# Combined_Board_BMI088.net
KiCad netlist of a schematic drawn in EAGLE
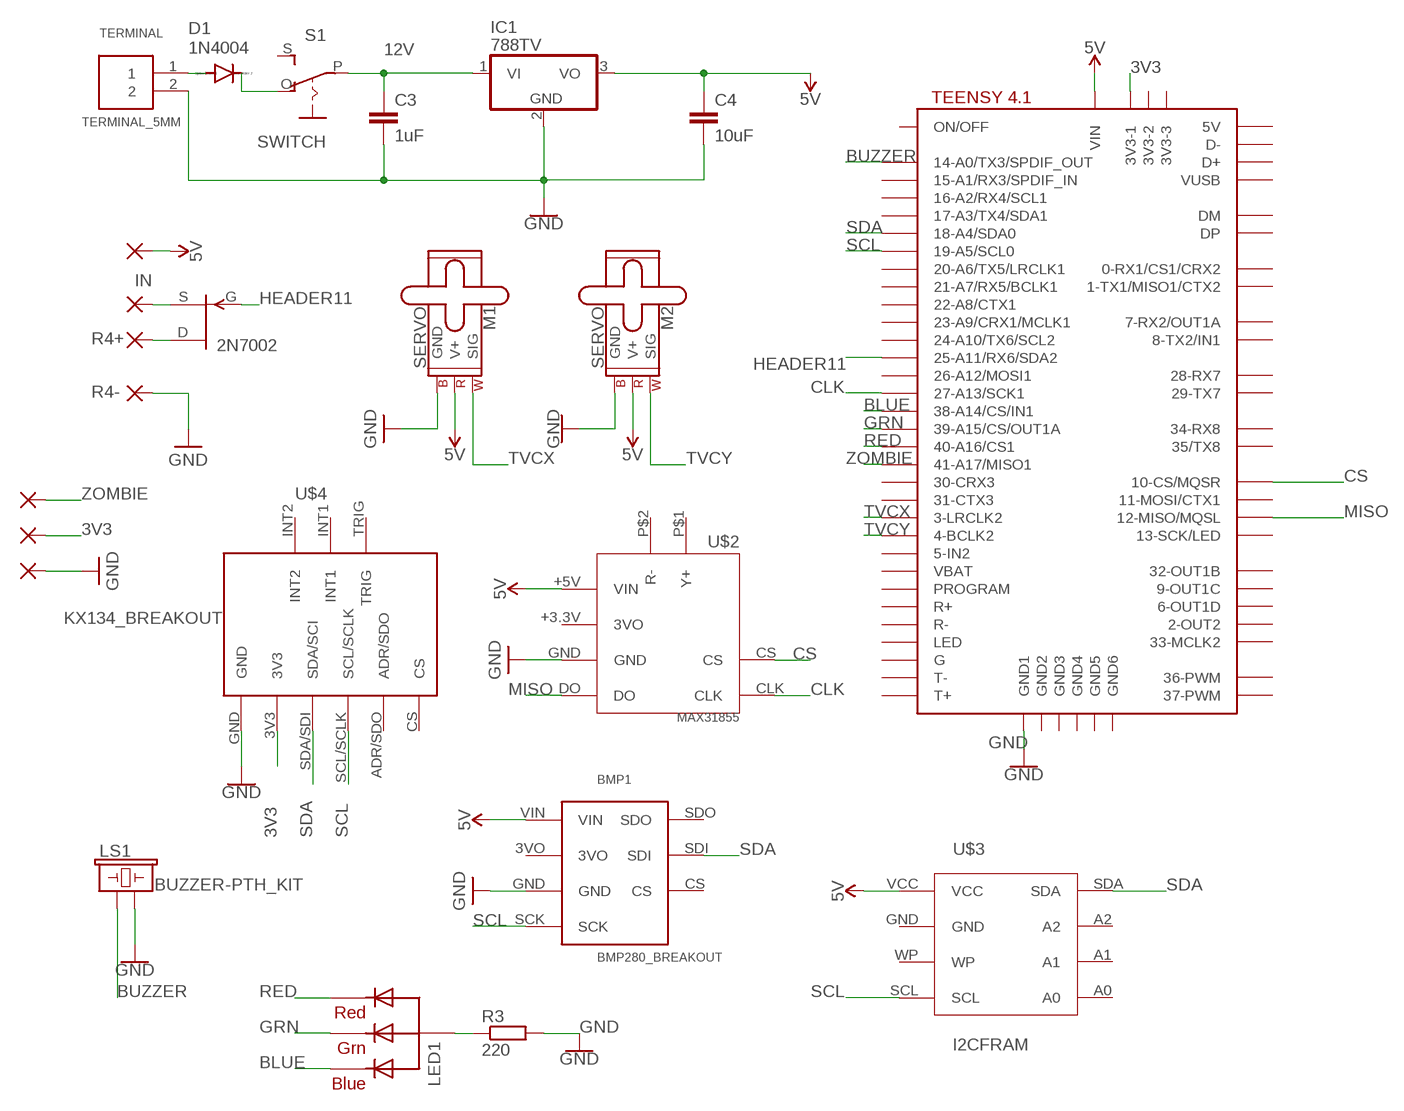
[diagram p0: schematic, sheet 1]

(export (version "E")
  (design (tool "Eeschema 10.0.6"))
  (components
    (comp (ref "2N7002")
      (value "2N3819")
      (footprint "eagle-import:TO92")
      (libsource (lib "eagle-import") (part "2N3819"))
    )
    (comp (ref "5V")
      (value "0")
      (footprint "eagle-import:1,6_0,8")
      (libsource (lib "eagle-import") (part "1,6/0,8"))
    )
    (comp (ref "BMP1")
      (value "BMP280_BREAKOUT")
      (footprint "eagle-import:BMP280_BREAKOUT")
      (libsource (lib "eagle-import") (part "BMP280_BREAKOUT"))
    )
    (comp (ref "C3")
      (value "1uF")
      (footprint "eagle-import:CAP-PTH-2.54")
      (libsource (lib "eagle-import") (part "22PF-PTH-2.54MM-200V-5%"))
    )
    (comp (ref "C4")
      (value "10uF")
      (footprint "eagle-import:CAP-PTH-2.54")
      (libsource (lib "eagle-import") (part "22PF-PTH-2.54MM-200V-5%"))
    )
    (comp (ref "D1")
      (value "1N4004")
      (footprint "eagle-import:DO41-10")
      (libsource (lib "eagle-import") (part "1N4004"))
    )
    (comp (ref "IC1")
      (value "788TV")
      (footprint "eagle-import:TO220V")
      (libsource (lib "eagle-import") (part "78TV8"))
    )
    (comp (ref "IN")
      (value "0")
      (footprint "eagle-import:1,6_0,8")
      (libsource (lib "eagle-import") (part "1,6/0,8"))
    )
    (comp (ref "LED1")
      (value "RGBLED_CA-5MM")
      (footprint "eagle-import:LED5MMRGB")
      (libsource (lib "eagle-import") (part "RGBLED_CA-5MM"))
    )
    (comp (ref "LS1")
      (value "BUZZER-PTH_KIT")
      (footprint "eagle-import:BUZZER-12MM-KIT")
      (libsource (lib "eagle-import") (part "BUZZER-PTH_KIT"))
    )
    (comp (ref "M1")
      (value "SERVO")
      (footprint "eagle-import:1X03")
      (libsource (lib "eagle-import") (part "SERVO"))
    )
    (comp (ref "M2")
      (value "SERVO")
      (footprint "eagle-import:1X03")
      (libsource (lib "eagle-import") (part "SERVO"))
    )
    (comp (ref "R3")
      (value "220")
      (footprint "eagle-import:0204_7")
      (libsource (lib "eagle-import") (part "R-EU_0204/7"))
    )
    (comp (ref "R4+")
      (value "0")
      (footprint "eagle-import:1,6_0,8")
      (libsource (lib "eagle-import") (part "1,6/0,8"))
    )
    (comp (ref "R4-")
      (value "0")
      (footprint "eagle-import:1,6_0,8")
      (libsource (lib "eagle-import") (part "1,6/0,8"))
    )
    (comp (ref "S1")
      (value "SWITCH")
      (footprint "eagle-import:EG1218")
      (libsource (lib "eagle-import") (part "EG1218S"))
    )
    (comp (ref "TERMINAL")
      (value "TERMINAL_5MM")
      (footprint "eagle-import:TERMINAL_5MM")
      (libsource (lib "eagle-import") (part "TERMINAL_5MM"))
    )
    (comp (ref "U$1")
      (value "TEENSY41")
      (footprint "eagle-import:TEENSY41")
      (libsource (lib "eagle-import") (part "TEENSY41"))
    )
    (comp (ref "U$2")
      (value "MAX31855")
      (footprint "eagle-import:MAX31855-BREAKOUT")
      (libsource (lib "eagle-import") (part "MAX31855"))
    )
    (comp (ref "U$3")
      (value "I2CFRAM")
      (footprint "eagle-import:I2CFRAM")
      (libsource (lib "eagle-import") (part "I2CFRAM"))
    )
    (comp (ref "U$4")
      (value "KX134_BREAKOUT")
      (footprint "eagle-import:KX134_BREAKOUT")
      (libsource (lib "eagle-import") (part "KX134_BREAKOUT"))
    )
    (comp (ref "ZOMBIE")
      (value "0")
      (footprint "eagle-import:1,6_0,8")
      (libsource (lib "eagle-import") (part "1,6/0,8"))
    )
    (comp (ref "ZOMBIE3V3")
      (value "0")
      (footprint "eagle-import:1,6_0,8")
      (libsource (lib "eagle-import") (part "1,6/0,8"))
    )
    (comp (ref "ZOMBIEGND")
      (value "0")
      (footprint "eagle-import:1,6_0,8")
      (libsource (lib "eagle-import") (part "1,6/0,8"))
    )
  )
  (nets
    (net (code "1") (name "/3V3") (class "Default")
      (node (ref "U$1") (pin "3V3-1") (pinfunction "3V3-1_3V3-1") (pintype "bidirectional"))
      (node (ref "U$4") (pin "3V3") (pinfunction "3V3_3V3") (pintype "bidirectional"))
      (node (ref "ZOMBIE3V3") (pin "1") (pinfunction "P_1") (pintype "passive"))
    )
    (net (code "2") (name "/12V") (class "Default")
      (node (ref "C3") (pin "1") (pinfunction "1_1") (pintype "passive"))
      (node (ref "IC1") (pin "1") (pinfunction "VI_1") (pintype "input"))
      (node (ref "S1") (pin "P") (pinfunction "P_P") (pintype "passive"))
    )
    (net (code "3") (name "/BLUE") (class "Default")
      (node (ref "LED1") (pin "4") (pinfunction "BLUE_4") (pintype "bidirectional"))
      (node (ref "U$1") (pin "38-A14/CS/IN1") (pinfunction "38-A14/CS/IN1_38-A14/CS/IN1") (pintype "bidirectional"))
    )
    (net (code "4") (name "/BUZZER") (class "Default")
      (node (ref "LS1") (pin "+") (pinfunction "1_+") (pintype "passive"))
      (node (ref "U$1") (pin "14-A0/TX3/SPDIF_OUT") (pinfunction "14-A0/TX3/SPDIF_OUT_14-A0/TX3/SPDIF_OUT") (pintype "bidirectional"))
    )
    (net (code "5") (name "/CLK") (class "Default")
      (node (ref "U$1") (pin "27-A13/SCK1") (pinfunction "27-A13/SCK1_27-A13/SCK1") (pintype "bidirectional"))
      (node (ref "U$2") (pin "CLK") (pinfunction "CLK_CLK") (pintype "input"))
    )
    (net (code "6") (name "/CS") (class "Default")
      (node (ref "U$1") (pin "10-CS\\MQSR") (pinfunction "10-CS/MQSR_10-CS\\MQSR") (pintype "bidirectional"))
      (node (ref "U$2") (pin "CS") (pinfunction "CS_CS") (pintype "input"))
    )
    (net (code "7") (name "/GRN") (class "Default")
      (node (ref "LED1") (pin "3") (pinfunction "GREEN_3") (pintype "bidirectional"))
      (node (ref "U$1") (pin "39-A15/CS/OUT1A") (pinfunction "39-A15/CS/OUT1A_39-A15/CS/OUT1A") (pintype "bidirectional"))
    )
    (net (code "8") (name "/HEADER11") (class "Default")
      (node (ref "2N7002") (pin "2") (pinfunction "G_2") (pintype "passive"))
      (node (ref "U$1") (pin "25-A11/RX6/SDA2") (pinfunction "25-A11/RX6/SDA2_25-A11/RX6/SDA2") (pintype "bidirectional"))
    )
    (net (code "9") (name "/IN") (class "Default")
      (node (ref "2N7002") (pin "3") (pinfunction "S_3") (pintype "passive"))
      (node (ref "IN") (pin "1") (pinfunction "P_1") (pintype "passive"))
    )
    (net (code "10") (name "/MISO") (class "Default")
      (node (ref "U$1") (pin "12-MISO/MQSL") (pinfunction "12-MISO/MQSL_12-MISO/MQSL") (pintype "bidirectional"))
      (node (ref "U$2") (pin "DO") (pinfunction "DO_DO") (pintype "output"))
    )
    (net (code "11") (name "/RED") (class "Default")
      (node (ref "LED1") (pin "1") (pinfunction "RED_1") (pintype "bidirectional"))
      (node (ref "U$1") (pin "40-A16/CS1") (pinfunction "40-A16/CS1_40-A16/CS1") (pintype "bidirectional"))
    )
    (net (code "12") (name "/SCL") (class "Default")
      (node (ref "BMP1") (pin "SCK") (pinfunction "SCK_SCK") (pintype "bidirectional"))
      (node (ref "U$1") (pin "19-A5/SCL0") (pinfunction "19-A5/SCL0_19-A5/SCL0") (pintype "bidirectional"))
      (node (ref "U$3") (pin "SCL") (pinfunction "SCL_SCL") (pintype "bidirectional"))
      (node (ref "U$4") (pin "SCL/SCLK") (pinfunction "SCL/SCLK_SCL/SCLK") (pintype "bidirectional"))
    )
    (net (code "13") (name "/SDA") (class "Default")
      (node (ref "BMP1") (pin "SDI") (pinfunction "SDI_SDI") (pintype "bidirectional"))
      (node (ref "U$1") (pin "18-A4/SDA0") (pinfunction "18-A4/SDA0_18-A4/SDA0") (pintype "bidirectional"))
      (node (ref "U$3") (pin "SDA") (pinfunction "SDA_SDA") (pintype "bidirectional"))
      (node (ref "U$4") (pin "SDA/SDI") (pinfunction "SDA/SCI_SDA/SDI") (pintype "bidirectional"))
    )
    (net (code "14") (name "/TVCX") (class "Default")
      (node (ref "M1") (pin "1") (pinfunction "SIG_1") (pintype "bidirectional"))
      (node (ref "U$1") (pin "3-LRCLK2") (pinfunction "3-LRCLK2_3-LRCLK2") (pintype "bidirectional"))
    )
    (net (code "15") (name "/TVCY") (class "Default")
      (node (ref "M2") (pin "1") (pinfunction "SIG_1") (pintype "bidirectional"))
      (node (ref "U$1") (pin "4-BCLK2") (pinfunction "4-BCLK2_4-BCLK2") (pintype "bidirectional"))
    )
    (net (code "16") (name "/ZOMBIE") (class "Default")
      (node (ref "U$1") (pin "41-A17/MISO1") (pinfunction "41-A17/MISO1_41-A17/MISO1") (pintype "bidirectional"))
      (node (ref "ZOMBIE") (pin "1") (pinfunction "P_1") (pintype "passive"))
    )
    (net (code "17") (name "5V") (class "Default")
      (node (ref "5V") (pin "1") (pinfunction "P_1") (pintype "passive"))
      (node (ref "BMP1") (pin "VIN") (pinfunction "VIN_VIN") (pintype "bidirectional"))
      (node (ref "C4") (pin "1") (pinfunction "1_1") (pintype "passive"))
      (node (ref "IC1") (pin "3") (pinfunction "VO_3") (pintype "passive"))
      (node (ref "M1") (pin "2") (pinfunction "V+_2") (pintype "bidirectional"))
      (node (ref "M2") (pin "2") (pinfunction "V+_2") (pintype "bidirectional"))
      (node (ref "U$1") (pin "VIN") (pinfunction "VIN_VIN") (pintype "bidirectional"))
      (node (ref "U$2") (pin "+5V") (pinfunction "VIN_+5V") (pintype "input"))
      (node (ref "U$3") (pin "VCC") (pinfunction "VCC_VCC") (pintype "bidirectional"))
    )
    (net (code "18") (name "GND") (class "Default")
      (node (ref "BMP1") (pin "GND") (pinfunction "GND_GND") (pintype "bidirectional"))
      (node (ref "C3") (pin "2") (pinfunction "2_2") (pintype "passive"))
      (node (ref "C4") (pin "2") (pinfunction "2_2") (pintype "passive"))
      (node (ref "IC1") (pin "2") (pinfunction "GND_2") (pintype "passive"))
      (node (ref "LS1") (pin "-") (pinfunction "2_-") (pintype "passive"))
      (node (ref "M1") (pin "3") (pinfunction "GND_3") (pintype "bidirectional"))
      (node (ref "M2") (pin "3") (pinfunction "GND_3") (pintype "bidirectional"))
      (node (ref "R3") (pin "2") (pinfunction "2_2") (pintype "passive"))
      (node (ref "R4-") (pin "1") (pinfunction "P_1") (pintype "passive"))
      (node (ref "TERMINAL") (pin "2") (pinfunction "2_2") (pintype "bidirectional"))
      (node (ref "U$1") (pin "GND1") (pinfunction "GND1_GND1") (pintype "bidirectional"))
      (node (ref "U$2") (pin "GND") (pinfunction "GND_GND") (pintype "input"))
      (node (ref "U$4") (pin "GND") (pinfunction "GND_GND") (pintype "bidirectional"))
      (node (ref "ZOMBIEGND") (pin "1") (pinfunction "P_1") (pintype "passive"))
    )
    (net (code "19") (name "Net-(2N7002-D)") (class "Default")
      (node (ref "2N7002") (pin "1") (pinfunction "D_1") (pintype "passive"))
      (node (ref "R4+") (pin "1") (pinfunction "P_1") (pintype "passive"))
    )
    (net (code "20") (name "Net-(D1-PadA)") (class "Default")
      (node (ref "D1") (pin "A") (pinfunction "A_A") (pintype "passive"))
      (node (ref "TERMINAL") (pin "1") (pinfunction "1_1") (pintype "bidirectional"))
    )
    (net (code "21") (name "Net-(D1-PadC)") (class "Default")
      (node (ref "D1") (pin "C") (pinfunction "C_C") (pintype "passive"))
      (node (ref "S1") (pin "O") (pinfunction "O_O") (pintype "passive"))
    )
    (net (code "22") (name "Net-(LED1-VCC)") (class "Default")
      (node (ref "LED1") (pin "2") (pinfunction "VCC_2") (pintype "bidirectional"))
      (node (ref "R3") (pin "1") (pinfunction "1_1") (pintype "passive"))
    )
    (net (code "23") (name "unconnected-(BMP1-Pad3VO)") (class "Default")
      (node (ref "BMP1") (pin "3VO") (pinfunction "3VO_3VO") (pintype "bidirectional"))
    )
    (net (code "24") (name "unconnected-(BMP1-PadCS)") (class "Default")
      (node (ref "BMP1") (pin "CS") (pinfunction "CS_CS") (pintype "bidirectional"))
    )
    (net (code "25") (name "unconnected-(BMP1-PadSDO)") (class "Default")
      (node (ref "BMP1") (pin "SDO") (pinfunction "SDO_SDO") (pintype "bidirectional"))
    )
    (net (code "26") (name "unconnected-(S1-PadS)") (class "Default")
      (node (ref "S1") (pin "S") (pinfunction "S_S") (pintype "passive"))
    )
    (net (code "27") (name "unconnected-(U$1-5V-Pad+5V)") (class "Default")
      (node (ref "U$1") (pin "+5V") (pinfunction "5V_+5V") (pintype "bidirectional"))
    )
    (net (code "28") (name "unconnected-(U$1-8-TX2{slash}IN1-Pad8-TX2{slash}IN2)") (class "Default")
      (node (ref "U$1") (pin "8-TX2/IN2") (pinfunction "8-TX2/IN1_8-TX2/IN2") (pintype "bidirectional"))
    )
    (net (code "29") (name "unconnected-(U$1-35{slash}TX8-Pad35-TX8)") (class "Default")
      (node (ref "U$1") (pin "35-TX8") (pinfunction "35/TX8_35-TX8") (pintype "bidirectional"))
    )
    (net (code "30") (name "unconnected-(U$1-Pad0-RX1{slash}CS1{slash}CRX2)") (class "Default")
      (node (ref "U$1") (pin "0-RX1/CS1/CRX2") (pinfunction "0-RX1/CS1/CRX2_0-RX1/CS1/CRX2") (pintype "bidirectional"))
    )
    (net (code "31") (name "unconnected-(U$1-Pad1-TX1{slash}MISO1{slash}CTX2)") (class "Default")
      (node (ref "U$1") (pin "1-TX1/MISO1/CTX2") (pinfunction "1-TX1/MISO1/CTX2_1-TX1/MISO1/CTX2") (pintype "bidirectional"))
    )
    (net (code "32") (name "unconnected-(U$1-Pad2-OUT2)") (class "Default")
      (node (ref "U$1") (pin "2-OUT2") (pinfunction "2-OUT2_2-OUT2") (pintype "bidirectional"))
    )
    (net (code "33") (name "unconnected-(U$1-Pad3V3-2)") (class "Default")
      (node (ref "U$1") (pin "3V3-2") (pinfunction "3V3-2_3V3-2") (pintype "bidirectional"))
    )
    (net (code "34") (name "unconnected-(U$1-Pad3V3-3)") (class "Default")
      (node (ref "U$1") (pin "3V3-3") (pinfunction "3V3-3_3V3-3") (pintype "bidirectional"))
    )
    (net (code "35") (name "unconnected-(U$1-Pad5-IN2)") (class "Default")
      (node (ref "U$1") (pin "5-IN2") (pinfunction "5-IN2_5-IN2") (pintype "bidirectional"))
    )
    (net (code "36") (name "unconnected-(U$1-Pad6-OUT1D)") (class "Default")
      (node (ref "U$1") (pin "6-OUT1D") (pinfunction "6-OUT1D_6-OUT1D") (pintype "bidirectional"))
    )
    (net (code "37") (name "unconnected-(U$1-Pad7-RX2{slash}OUT1A)") (class "Default")
      (node (ref "U$1") (pin "7-RX2/OUT1A") (pinfunction "7-RX2/OUT1A_7-RX2/OUT1A") (pintype "bidirectional"))
    )
    (net (code "38") (name "unconnected-(U$1-Pad9-OUT1C)") (class "Default")
      (node (ref "U$1") (pin "9-OUT1C") (pinfunction "9-OUT1C_9-OUT1C") (pintype "bidirectional"))
    )
    (net (code "39") (name "unconnected-(U$1-Pad11-MOSI{slash}CTX1)") (class "Default")
      (node (ref "U$1") (pin "11-MOSI/CTX1") (pinfunction "11-MOSI/CTX1_11-MOSI/CTX1") (pintype "bidirectional"))
    )
    (net (code "40") (name "unconnected-(U$1-Pad13-SCK{slash}LED)") (class "Default")
      (node (ref "U$1") (pin "13-SCK/LED") (pinfunction "13-SCK/LED_13-SCK/LED") (pintype "bidirectional"))
    )
    (net (code "41") (name "unconnected-(U$1-Pad15-A1{slash}RX3{slash}SPDIF_IN)") (class "Default")
      (node (ref "U$1") (pin "15-A1/RX3/SPDIF_IN") (pinfunction "15-A1/RX3/SPDIF_IN_15-A1/RX3/SPDIF_IN") (pintype "bidirectional"))
    )
    (net (code "42") (name "unconnected-(U$1-Pad16-A2{slash}RX4{slash}SCL1)") (class "Default")
      (node (ref "U$1") (pin "16-A2/RX4/SCL1") (pinfunction "16-A2/RX4/SCL1_16-A2/RX4/SCL1") (pintype "bidirectional"))
    )
    (net (code "43") (name "unconnected-(U$1-Pad17-A3{slash}TX4{slash}SDA1)") (class "Default")
      (node (ref "U$1") (pin "17-A3/TX4/SDA1") (pinfunction "17-A3/TX4/SDA1_17-A3/TX4/SDA1") (pintype "bidirectional"))
    )
    (net (code "44") (name "unconnected-(U$1-Pad20-A6{slash}TX5{slash}LRCLK1)") (class "Default")
      (node (ref "U$1") (pin "20-A6/TX5/LRCLK1") (pinfunction "20-A6/TX5/LRCLK1_20-A6/TX5/LRCLK1") (pintype "bidirectional"))
    )
    (net (code "45") (name "unconnected-(U$1-Pad21-A7{slash}RX5{slash}BCLK1)") (class "Default")
      (node (ref "U$1") (pin "21-A7/RX5/BCLK1") (pinfunction "21-A7/RX5/BCLK1_21-A7/RX5/BCLK1") (pintype "bidirectional"))
    )
    (net (code "46") (name "unconnected-(U$1-Pad22-A8{slash}CTX1)") (class "Default")
      (node (ref "U$1") (pin "22-A8/CTX1") (pinfunction "22-A8/CTX1_22-A8/CTX1") (pintype "bidirectional"))
    )
    (net (code "47") (name "unconnected-(U$1-Pad23-A9{slash}CRX1{slash}MCLK1)") (class "Default")
      (node (ref "U$1") (pin "23-A9/CRX1/MCLK1") (pinfunction "23-A9/CRX1/MCLK1_23-A9/CRX1/MCLK1") (pintype "bidirectional"))
    )
    (net (code "48") (name "unconnected-(U$1-Pad24-A10{slash}TX6{slash}SCL2)") (class "Default")
      (node (ref "U$1") (pin "24-A10/TX6/SCL2") (pinfunction "24-A10/TX6/SCL2_24-A10/TX6/SCL2") (pintype "bidirectional"))
    )
    (net (code "49") (name "unconnected-(U$1-Pad26-A12{slash}MOSI1)") (class "Default")
      (node (ref "U$1") (pin "26-A12/MOSI1") (pinfunction "26-A12/MOSI1_26-A12/MOSI1") (pintype "bidirectional"))
    )
    (net (code "50") (name "unconnected-(U$1-Pad28-RX7)") (class "Default")
      (node (ref "U$1") (pin "28-RX7") (pinfunction "28-RX7_28-RX7") (pintype "bidirectional"))
    )
    (net (code "51") (name "unconnected-(U$1-Pad29-TX7)") (class "Default")
      (node (ref "U$1") (pin "29-TX7") (pinfunction "29-TX7_29-TX7") (pintype "bidirectional"))
    )
    (net (code "52") (name "unconnected-(U$1-Pad30-CRX3)") (class "Default")
      (node (ref "U$1") (pin "30-CRX3") (pinfunction "30-CRX3_30-CRX3") (pintype "bidirectional"))
    )
    (net (code "53") (name "unconnected-(U$1-Pad31-CTX3)") (class "Default")
      (node (ref "U$1") (pin "31-CTX3") (pinfunction "31-CTX3_31-CTX3") (pintype "bidirectional"))
    )
    (net (code "54") (name "unconnected-(U$1-Pad32-OUT1B)") (class "Default")
      (node (ref "U$1") (pin "32-OUT1B") (pinfunction "32-OUT1B_32-OUT1B") (pintype "bidirectional"))
    )
    (net (code "55") (name "unconnected-(U$1-Pad33-MCLK2)") (class "Default")
      (node (ref "U$1") (pin "33-MCLK2") (pinfunction "33-MCLK2_33-MCLK2") (pintype "bidirectional"))
    )
    (net (code "56") (name "unconnected-(U$1-Pad34-RX8)") (class "Default")
      (node (ref "U$1") (pin "34-RX8") (pinfunction "34-RX8_34-RX8") (pintype "bidirectional"))
    )
    (net (code "57") (name "unconnected-(U$1-Pad36-PWM)") (class "Default")
      (node (ref "U$1") (pin "36-PWM") (pinfunction "36-PWM_36-PWM") (pintype "bidirectional"))
    )
    (net (code "58") (name "unconnected-(U$1-Pad37-PWM)") (class "Default")
      (node (ref "U$1") (pin "37-PWM") (pinfunction "37-PWM_37-PWM") (pintype "bidirectional"))
    )
    (net (code "59") (name "unconnected-(U$1-PadD+)") (class "Default")
      (node (ref "U$1") (pin "D+") (pinfunction "D+_D+") (pintype "bidirectional"))
    )
    (net (code "60") (name "unconnected-(U$1-PadD-)") (class "Default")
      (node (ref "U$1") (pin "D-") (pinfunction "D-_D-") (pintype "bidirectional"))
    )
    (net (code "61") (name "unconnected-(U$1-PadDM)") (class "Default")
      (node (ref "U$1") (pin "DM") (pinfunction "DM_DM") (pintype "bidirectional"))
    )
    (net (code "62") (name "unconnected-(U$1-PadDP)") (class "Default")
      (node (ref "U$1") (pin "DP") (pinfunction "DP_DP") (pintype "bidirectional"))
    )
    (net (code "63") (name "unconnected-(U$1-PadG)") (class "Default")
      (node (ref "U$1") (pin "G") (pinfunction "G_G") (pintype "bidirectional"))
    )
    (net (code "64") (name "unconnected-(U$1-PadGND2)") (class "Default")
      (node (ref "U$1") (pin "GND2") (pinfunction "GND2_GND2") (pintype "bidirectional"))
    )
    (net (code "65") (name "unconnected-(U$1-PadGND3)") (class "Default")
      (node (ref "U$1") (pin "GND3") (pinfunction "GND3_GND3") (pintype "bidirectional"))
    )
    (net (code "66") (name "unconnected-(U$1-PadGND4)") (class "Default")
      (node (ref "U$1") (pin "GND4") (pinfunction "GND4_GND4") (pintype "bidirectional"))
    )
    (net (code "67") (name "unconnected-(U$1-PadGND5)") (class "Default")
      (node (ref "U$1") (pin "GND5") (pinfunction "GND5_GND5") (pintype "bidirectional"))
    )
    (net (code "68") (name "unconnected-(U$1-PadGND6)") (class "Default")
      (node (ref "U$1") (pin "GND6") (pinfunction "GND6_GND6") (pintype "bidirectional"))
    )
    (net (code "69") (name "unconnected-(U$1-PadLED)") (class "Default")
      (node (ref "U$1") (pin "LED") (pinfunction "LED_LED") (pintype "bidirectional"))
    )
    (net (code "70") (name "unconnected-(U$1-PadON{slash}OFF)") (class "Default")
      (node (ref "U$1") (pin "ON/OFF") (pinfunction "ON/OFF_ON/OFF") (pintype "bidirectional"))
    )
    (net (code "71") (name "unconnected-(U$1-PadPROGRAM)") (class "Default")
      (node (ref "U$1") (pin "PROGRAM") (pinfunction "PROGRAM_PROGRAM") (pintype "bidirectional"))
    )
    (net (code "72") (name "unconnected-(U$1-PadR+)") (class "Default")
      (node (ref "U$1") (pin "R+") (pinfunction "R+_R+") (pintype "bidirectional"))
    )
    (net (code "73") (name "unconnected-(U$1-PadR-)") (class "Default")
      (node (ref "U$1") (pin "R-") (pinfunction "R-_R-") (pintype "bidirectional"))
    )
    (net (code "74") (name "unconnected-(U$1-PadT+)") (class "Default")
      (node (ref "U$1") (pin "T+") (pinfunction "T+_T+") (pintype "bidirectional"))
    )
    (net (code "75") (name "unconnected-(U$1-PadT-)") (class "Default")
      (node (ref "U$1") (pin "T-") (pinfunction "T-_T-") (pintype "bidirectional"))
    )
    (net (code "76") (name "unconnected-(U$1-PadVBAT)") (class "Default")
      (node (ref "U$1") (pin "VBAT") (pinfunction "VBAT_VBAT") (pintype "bidirectional"))
    )
    (net (code "77") (name "unconnected-(U$1-PadVUSB)") (class "Default")
      (node (ref "U$1") (pin "VUSB") (pinfunction "VUSB_VUSB") (pintype "bidirectional"))
    )
    (net (code "78") (name "unconnected-(U$2-3VO-Pad+3.3V)") (class "Default")
      (node (ref "U$2") (pin "+3.3V") (pinfunction "3VO_+3.3V") (pintype "output"))
    )
    (net (code "79") (name "unconnected-(U$2-R--PadP$2)") (class "Default")
      (node (ref "U$2") (pin "P$2") (pinfunction "R-_P$2") (pintype "bidirectional"))
    )
    (net (code "80") (name "unconnected-(U$2-Y+-PadP$1)") (class "Default")
      (node (ref "U$2") (pin "P$1") (pinfunction "Y+_P$1") (pintype "bidirectional"))
    )
    (net (code "81") (name "unconnected-(U$3-PadA0)") (class "Default")
      (node (ref "U$3") (pin "A0") (pinfunction "A0_A0") (pintype "bidirectional"))
    )
    (net (code "82") (name "unconnected-(U$3-PadA1)") (class "Default")
      (node (ref "U$3") (pin "A1") (pinfunction "A1_A1") (pintype "bidirectional"))
    )
    (net (code "83") (name "unconnected-(U$3-PadA2)") (class "Default")
      (node (ref "U$3") (pin "A2") (pinfunction "A2_A2") (pintype "bidirectional"))
    )
    (net (code "84") (name "unconnected-(U$3-PadGND)") (class "Default")
      (node (ref "U$3") (pin "GND") (pinfunction "GND_GND") (pintype "bidirectional"))
    )
    (net (code "85") (name "unconnected-(U$3-PadWP)") (class "Default")
      (node (ref "U$3") (pin "WP") (pinfunction "WP_WP") (pintype "bidirectional"))
    )
    (net (code "86") (name "unconnected-(U$4-PadADR{slash}SDO)") (class "Default")
      (node (ref "U$4") (pin "ADR/SDO") (pinfunction "ADR/SDO_ADR/SDO") (pintype "bidirectional"))
    )
    (net (code "87") (name "unconnected-(U$4-PadCS)") (class "Default")
      (node (ref "U$4") (pin "CS") (pinfunction "CS_CS") (pintype "bidirectional"))
    )
    (net (code "88") (name "unconnected-(U$4-PadINT1)") (class "Default")
      (node (ref "U$4") (pin "INT1") (pinfunction "INT1_INT1") (pintype "bidirectional"))
    )
    (net (code "89") (name "unconnected-(U$4-PadINT2)") (class "Default")
      (node (ref "U$4") (pin "INT2") (pinfunction "INT2_INT2") (pintype "bidirectional"))
    )
    (net (code "90") (name "unconnected-(U$4-PadTRIG)") (class "Default")
      (node (ref "U$4") (pin "TRIG") (pinfunction "TRIG_TRIG") (pintype "bidirectional"))
    )
  )
)
